# metal_detector_circuit.net
KiCad netlist of a schematic drawn in EAGLE
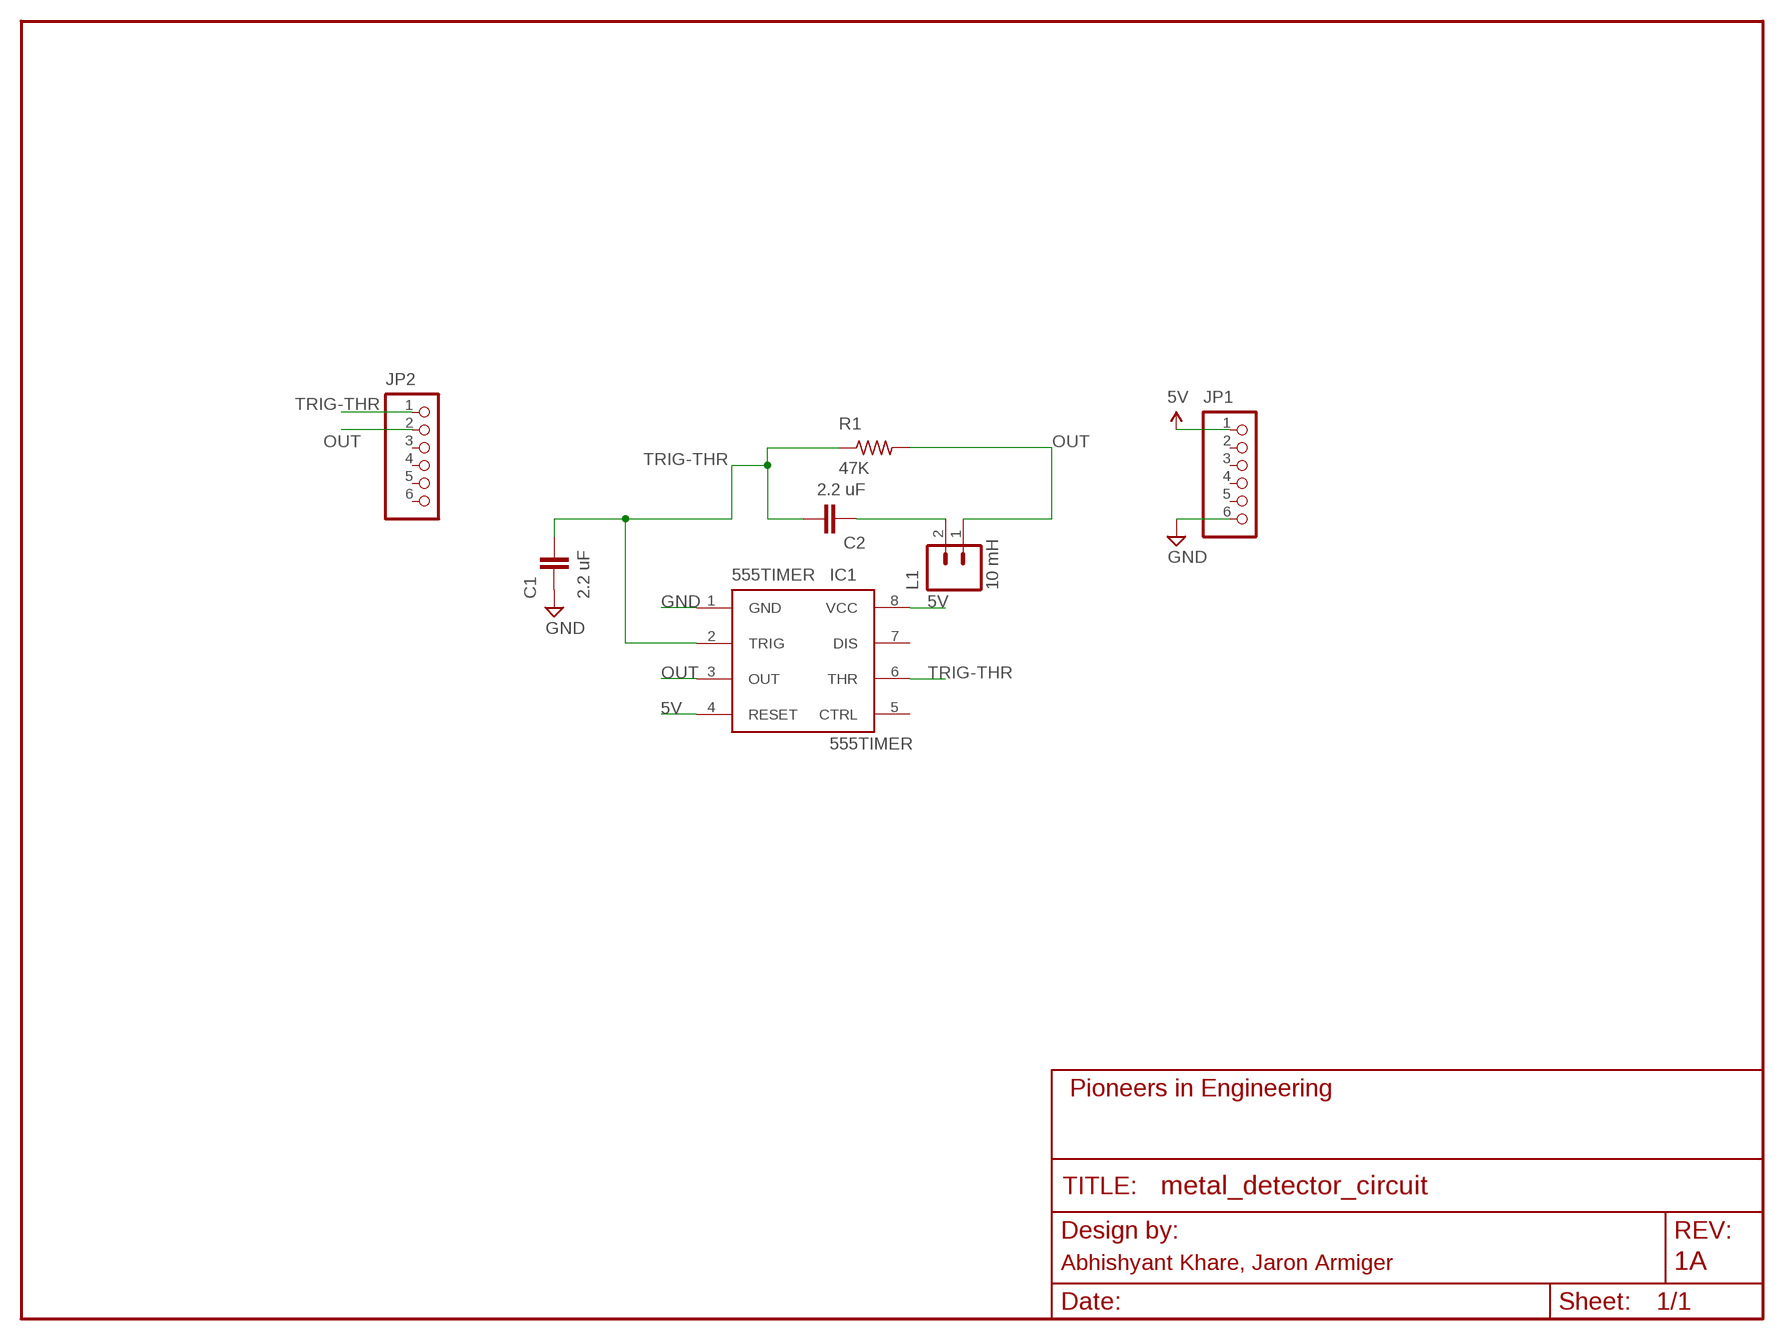
[diagram p0: schematic, sheet 1]

(export (version "E")
  (design (tool "Eeschema 10.0.6"))
  (components
    (comp (ref "C1")
      (value "2.2 uF")
      (footprint "eagle-import:0603-CAP")
      (libsource (lib "eagle-import") (part "CAP0603-CAP"))
    )
    (comp (ref "C2")
      (value "2.2 uF")
      (footprint "eagle-import:0603-CAP")
      (libsource (lib "eagle-import") (part "CAP0603-CAP"))
    )
    (comp (ref "IC1")
      (value "555TIMER")
      (footprint "eagle-import:8-PIN_SOIC")
      (libsource (lib "eagle-import") (part "555TIMER"))
    )
    (comp (ref "JP1")
      (value "PINHD-1X6")
      (footprint "eagle-import:1X06")
      (fields (field (name "PARTNUMBER") "965"))
      (libsource (lib "eagle-import") (part "PINHD-1X6"))
    )
    (comp (ref "JP2")
      (value "PINHD-1X6")
      (footprint "eagle-import:1X06")
      (fields (field (name "PARTNUMBER") "965"))
      (libsource (lib "eagle-import") (part "PINHD-1X6"))
    )
    (comp (ref "L1")
      (value "10 mH")
      (footprint "eagle-import:1X02")
      (libsource (lib "eagle-import") (part "M02PTH"))
    )
    (comp (ref "R1")
      (value "47K")
      (footprint "eagle-import:R0603")
      (libsource (lib "eagle-import") (part "R-US_R0603"))
    )
  )
  (nets
    (net (code "1") (name "/OUT") (class "Default")
      (node (ref "IC1") (pin "3") (pinfunction "OUT_3") (pintype "bidirectional"))
      (node (ref "JP2") (pin "2") (pinfunction "2_2") (pintype "passive"))
      (node (ref "L1") (pin "1") (pinfunction "1_1") (pintype "passive"))
      (node (ref "R1") (pin "2") (pinfunction "2_2") (pintype "passive"))
    )
    (net (code "2") (name "/TRIG-THR") (class "Default")
      (node (ref "C1") (pin "2") (pinfunction "2_2") (pintype "passive"))
      (node (ref "C2") (pin "2") (pinfunction "2_2") (pintype "passive"))
      (node (ref "IC1") (pin "2") (pinfunction "TRIG_2") (pintype "bidirectional"))
      (node (ref "IC1") (pin "6") (pinfunction "THR_6") (pintype "bidirectional"))
      (node (ref "JP2") (pin "1") (pinfunction "1_1") (pintype "passive"))
      (node (ref "R1") (pin "1") (pinfunction "1_1") (pintype "passive"))
    )
    (net (code "3") (name "5V") (class "Default")
      (node (ref "IC1") (pin "4") (pinfunction "RESET_4") (pintype "bidirectional"))
      (node (ref "IC1") (pin "8") (pinfunction "VCC_8") (pintype "bidirectional"))
      (node (ref "JP1") (pin "1") (pinfunction "1_1") (pintype "passive"))
    )
    (net (code "4") (name "GND") (class "Default")
      (node (ref "C1") (pin "1") (pinfunction "1_1") (pintype "passive"))
      (node (ref "IC1") (pin "1") (pinfunction "GND_1") (pintype "bidirectional"))
      (node (ref "JP1") (pin "6") (pinfunction "6_6") (pintype "passive"))
    )
    (net (code "5") (name "Net-(C2-Pad1)") (class "Default")
      (node (ref "C2") (pin "1") (pinfunction "1_1") (pintype "passive"))
      (node (ref "L1") (pin "2") (pinfunction "2_2") (pintype "passive"))
    )
    (net (code "6") (name "unconnected-(IC1-CTRL-Pad5)") (class "Default")
      (node (ref "IC1") (pin "5") (pinfunction "CTRL_5") (pintype "bidirectional"))
    )
    (net (code "7") (name "unconnected-(IC1-DIS-Pad7)") (class "Default")
      (node (ref "IC1") (pin "7") (pinfunction "DIS_7") (pintype "bidirectional"))
    )
    (net (code "8") (name "unconnected-(JP1-Pad2)") (class "Default")
      (node (ref "JP1") (pin "2") (pinfunction "2_2") (pintype "passive"))
    )
    (net (code "9") (name "unconnected-(JP1-Pad3)") (class "Default")
      (node (ref "JP1") (pin "3") (pinfunction "3_3") (pintype "passive"))
    )
    (net (code "10") (name "unconnected-(JP1-Pad4)") (class "Default")
      (node (ref "JP1") (pin "4") (pinfunction "4_4") (pintype "passive"))
    )
    (net (code "11") (name "unconnected-(JP1-Pad5)") (class "Default")
      (node (ref "JP1") (pin "5") (pinfunction "5_5") (pintype "passive"))
    )
    (net (code "12") (name "unconnected-(JP2-Pad3)") (class "Default")
      (node (ref "JP2") (pin "3") (pinfunction "3_3") (pintype "passive"))
    )
    (net (code "13") (name "unconnected-(JP2-Pad4)") (class "Default")
      (node (ref "JP2") (pin "4") (pinfunction "4_4") (pintype "passive"))
    )
    (net (code "14") (name "unconnected-(JP2-Pad5)") (class "Default")
      (node (ref "JP2") (pin "5") (pinfunction "5_5") (pintype "passive"))
    )
    (net (code "15") (name "unconnected-(JP2-Pad6)") (class "Default")
      (node (ref "JP2") (pin "6") (pinfunction "6_6") (pintype "passive"))
    )
  )
)
